# pi_rgb.net
KiCad netlist of a schematic drawn in EAGLE
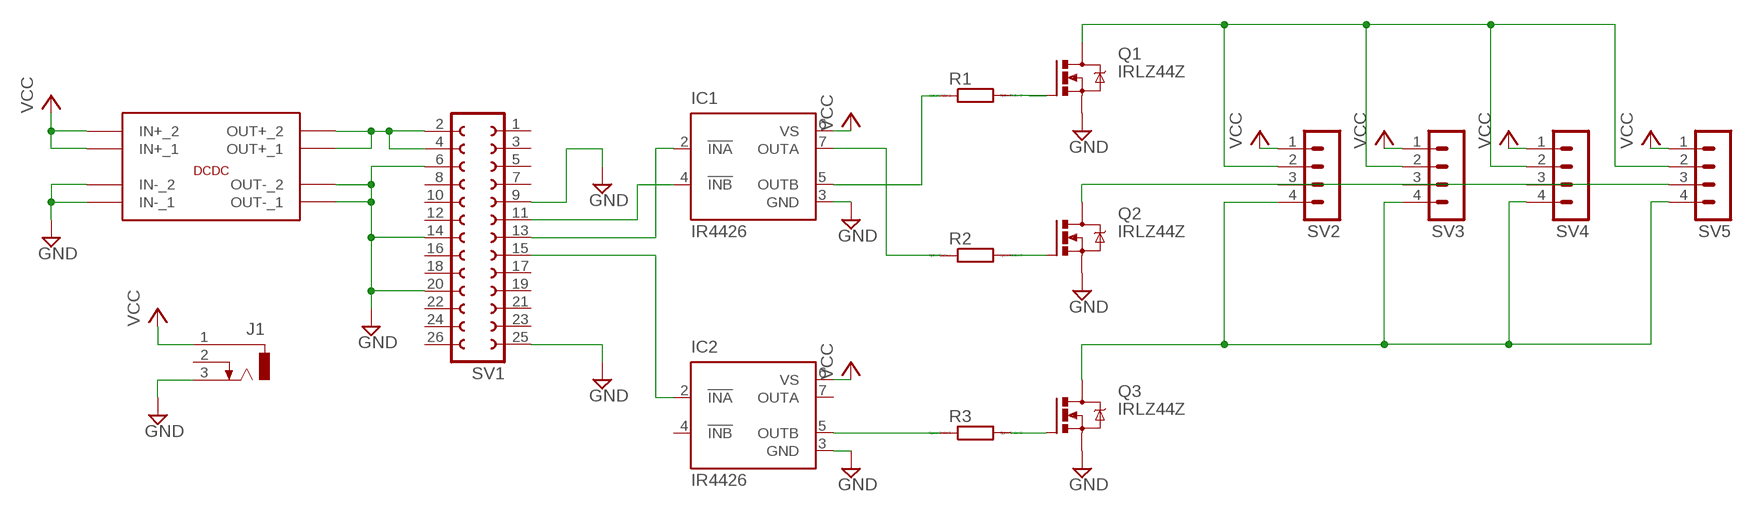
[diagram p0: schematic, sheet 1]

(export (version "E")
  (design (tool "Eeschema 10.0.6"))
  (components
    (comp (ref "5V")
      (value "DCDC")
      (footprint "eagle-import:DCDC")
      (libsource (lib "eagle-import") (part "DCDC"))
    )
    (comp (ref "IC1")
      (value "IR4426")
      (footprint "eagle-import:DIL08")
      (fields (field (name "MF") "INTERNATIONAL RECTIFIER(IR)") (field (name "MPN") "IR4426PBF"))
      (libsource (lib "eagle-import") (part "IR4426"))
    )
    (comp (ref "IC2")
      (value "IR4426")
      (footprint "eagle-import:DIL08")
      (fields (field (name "MF") "INTERNATIONAL RECTIFIER(IR)") (field (name "MPN") "IR4426PBF"))
      (libsource (lib "eagle-import") (part "IR4426"))
    )
    (comp (ref "J1")
      (value "DCJ0303")
      (footprint "eagle-import:DCJ0303")
      (libsource (lib "eagle-import") (part "DCJ0303"))
    )
    (comp (ref "Q1")
      (value "IRLZ44Z")
      (footprint "eagle-import:TO220BV")
      (libsource (lib "eagle-import") (part "IRLZ44Z"))
    )
    (comp (ref "Q2")
      (value "IRLZ44Z")
      (footprint "eagle-import:TO220BV")
      (libsource (lib "eagle-import") (part "IRLZ44Z"))
    )
    (comp (ref "Q3")
      (value "IRLZ44Z")
      (footprint "eagle-import:TO220BV")
      (libsource (lib "eagle-import") (part "IRLZ44Z"))
    )
    (comp (ref "R1")
      (value "R-EU_0204_5")
      (footprint "eagle-import:0204_5")
      (libsource (lib "eagle-import") (part "R-EU_0204_5"))
    )
    (comp (ref "R2")
      (value "R-EU_0204_5")
      (footprint "eagle-import:0204_5")
      (libsource (lib "eagle-import") (part "R-EU_0204_5"))
    )
    (comp (ref "R3")
      (value "R-EU_0204_5")
      (footprint "eagle-import:0204_5")
      (libsource (lib "eagle-import") (part "R-EU_0204_5"))
    )
    (comp (ref "SV1")
      (value "FE13-2")
      (footprint "eagle-import:FE13-2")
      (libsource (lib "eagle-import") (part "FE13-2"))
    )
    (comp (ref "SV2")
      (value "MA04-1")
      (footprint "eagle-import:MA04-1")
      (libsource (lib "eagle-import") (part "MA04-1"))
    )
    (comp (ref "SV3")
      (value "MA04-1")
      (footprint "eagle-import:MA04-1")
      (libsource (lib "eagle-import") (part "MA04-1"))
    )
    (comp (ref "SV4")
      (value "MA04-1")
      (footprint "eagle-import:MA04-1")
      (libsource (lib "eagle-import") (part "MA04-1"))
    )
    (comp (ref "SV5")
      (value "MA04-1")
      (footprint "eagle-import:MA04-1")
      (libsource (lib "eagle-import") (part "MA04-1"))
    )
  )
  (nets
    (net (code "1") (name "GND") (class "Default")
      (node (ref "5V") (pin "IN-_1") (pinfunction "IN-_1_IN-_1") (pintype "bidirectional"))
      (node (ref "5V") (pin "IN-_2") (pinfunction "IN-_2_IN-_2") (pintype "bidirectional"))
      (node (ref "5V") (pin "OUT-_1") (pinfunction "OUT-_1_OUT-_1") (pintype "bidirectional"))
      (node (ref "5V") (pin "OUT-_2") (pinfunction "OUT-_2_OUT-_2") (pintype "bidirectional"))
      (node (ref "IC1") (pin "3") (pinfunction "GND_3") (pintype "power_in"))
      (node (ref "IC2") (pin "3") (pinfunction "GND_3") (pintype "power_in"))
      (node (ref "J1") (pin "3") (pinfunction "3_3") (pintype "passive"))
      (node (ref "Q1") (pin "S") (pinfunction "S_S") (pintype "passive"))
      (node (ref "Q2") (pin "S") (pinfunction "S_S") (pintype "passive"))
      (node (ref "Q3") (pin "S") (pinfunction "S_S") (pintype "passive"))
      (node (ref "SV1") (pin "14") (pinfunction "14_14") (pintype "passive"))
      (node (ref "SV1") (pin "20") (pinfunction "20_20") (pintype "passive"))
      (node (ref "SV1") (pin "25") (pinfunction "25_25") (pintype "passive"))
      (node (ref "SV1") (pin "6") (pinfunction "6_6") (pintype "passive"))
      (node (ref "SV1") (pin "9") (pinfunction "9_9") (pintype "passive"))
    )
    (net (code "2") (name "Net-(5V-OUT+_1)") (class "Default")
      (node (ref "5V") (pin "OUT+2") (pinfunction "OUT+_1_OUT+2") (pintype "bidirectional"))
      (node (ref "5V") (pin "OUT+_1") (pinfunction "OUT+_2_OUT+_1") (pintype "bidirectional"))
      (node (ref "SV1") (pin "2") (pinfunction "2_2") (pintype "passive"))
      (node (ref "SV1") (pin "4") (pinfunction "4_4") (pintype "passive"))
    )
    (net (code "3") (name "Net-(IC1-OUTA)") (class "Default")
      (node (ref "IC1") (pin "7") (pinfunction "OUTA_7") (pintype "output"))
      (node (ref "R2") (pin "1") (pinfunction "1_1") (pintype "passive"))
    )
    (net (code "4") (name "Net-(IC1-OUTB)") (class "Default")
      (node (ref "IC1") (pin "5") (pinfunction "OUTB_5") (pintype "output"))
      (node (ref "R1") (pin "1") (pinfunction "1_1") (pintype "passive"))
    )
    (net (code "5") (name "Net-(IC1-~{INA})") (class "Default")
      (node (ref "IC1") (pin "2") (pinfunction "~{INA}_2") (pintype "input"))
      (node (ref "SV1") (pin "13") (pinfunction "13_13") (pintype "passive"))
    )
    (net (code "6") (name "Net-(IC1-~{INB})") (class "Default")
      (node (ref "IC1") (pin "4") (pinfunction "~{INB}_4") (pintype "input"))
      (node (ref "SV1") (pin "11") (pinfunction "11_11") (pintype "passive"))
    )
    (net (code "7") (name "Net-(IC2-OUTB)") (class "Default")
      (node (ref "IC2") (pin "5") (pinfunction "OUTB_5") (pintype "output"))
      (node (ref "R3") (pin "1") (pinfunction "1_1") (pintype "passive"))
    )
    (net (code "8") (name "Net-(IC2-~{INA})") (class "Default")
      (node (ref "IC2") (pin "2") (pinfunction "~{INA}_2") (pintype "input"))
      (node (ref "SV1") (pin "15") (pinfunction "15_15") (pintype "passive"))
    )
    (net (code "9") (name "Net-(Q1-PadD)") (class "Default")
      (node (ref "Q1") (pin "D") (pinfunction "D_D") (pintype "passive"))
      (node (ref "SV2") (pin "2") (pinfunction "2_2") (pintype "passive"))
      (node (ref "SV3") (pin "2") (pinfunction "2_2") (pintype "passive"))
      (node (ref "SV4") (pin "2") (pinfunction "2_2") (pintype "passive"))
      (node (ref "SV5") (pin "2") (pinfunction "2_2") (pintype "passive"))
    )
    (net (code "10") (name "Net-(Q1-PadG)") (class "Default")
      (node (ref "Q1") (pin "G") (pinfunction "G_G") (pintype "passive"))
      (node (ref "R1") (pin "2") (pinfunction "2_2") (pintype "passive"))
    )
    (net (code "11") (name "Net-(Q2-PadD)") (class "Default")
      (node (ref "Q2") (pin "D") (pinfunction "D_D") (pintype "passive"))
      (node (ref "SV2") (pin "3") (pinfunction "3_3") (pintype "passive"))
      (node (ref "SV3") (pin "3") (pinfunction "3_3") (pintype "passive"))
      (node (ref "SV4") (pin "3") (pinfunction "3_3") (pintype "passive"))
      (node (ref "SV5") (pin "3") (pinfunction "3_3") (pintype "passive"))
    )
    (net (code "12") (name "Net-(Q2-PadG)") (class "Default")
      (node (ref "Q2") (pin "G") (pinfunction "G_G") (pintype "passive"))
      (node (ref "R2") (pin "2") (pinfunction "2_2") (pintype "passive"))
    )
    (net (code "13") (name "Net-(Q3-PadD)") (class "Default")
      (node (ref "Q3") (pin "D") (pinfunction "D_D") (pintype "passive"))
      (node (ref "SV2") (pin "4") (pinfunction "4_4") (pintype "passive"))
      (node (ref "SV3") (pin "4") (pinfunction "4_4") (pintype "passive"))
      (node (ref "SV4") (pin "4") (pinfunction "4_4") (pintype "passive"))
      (node (ref "SV5") (pin "4") (pinfunction "4_4") (pintype "passive"))
    )
    (net (code "14") (name "Net-(Q3-PadG)") (class "Default")
      (node (ref "Q3") (pin "G") (pinfunction "G_G") (pintype "passive"))
      (node (ref "R3") (pin "2") (pinfunction "2_2") (pintype "passive"))
    )
    (net (code "15") (name "VCC") (class "Default")
      (node (ref "5V") (pin "IN+_1") (pinfunction "IN+_1_IN+_1") (pintype "bidirectional"))
      (node (ref "5V") (pin "IN+_2") (pinfunction "IN+_2_IN+_2") (pintype "bidirectional"))
      (node (ref "IC1") (pin "6") (pinfunction "VS_6") (pintype "power_in"))
      (node (ref "IC2") (pin "6") (pinfunction "VS_6") (pintype "power_in"))
      (node (ref "J1") (pin "1") (pinfunction "1_1") (pintype "passive"))
      (node (ref "SV2") (pin "1") (pinfunction "1_1") (pintype "passive"))
      (node (ref "SV3") (pin "1") (pinfunction "1_1") (pintype "passive"))
      (node (ref "SV4") (pin "1") (pinfunction "1_1") (pintype "passive"))
      (node (ref "SV5") (pin "1") (pinfunction "1_1") (pintype "passive"))
    )
    (net (code "16") (name "unconnected-(IC2-OUTA-Pad7)") (class "Default")
      (node (ref "IC2") (pin "7") (pinfunction "OUTA_7") (pintype "output"))
    )
    (net (code "17") (name "unconnected-(IC2-~{INB}-Pad4)") (class "Default")
      (node (ref "IC2") (pin "4") (pinfunction "~{INB}_4") (pintype "input"))
    )
    (net (code "18") (name "unconnected-(J1-Pad2)") (class "Default")
      (node (ref "J1") (pin "2") (pinfunction "2_2") (pintype "passive"))
    )
    (net (code "19") (name "unconnected-(SV1-Pad1)") (class "Default")
      (node (ref "SV1") (pin "1") (pinfunction "1_1") (pintype "passive"))
    )
    (net (code "20") (name "unconnected-(SV1-Pad3)") (class "Default")
      (node (ref "SV1") (pin "3") (pinfunction "3_3") (pintype "passive"))
    )
    (net (code "21") (name "unconnected-(SV1-Pad5)") (class "Default")
      (node (ref "SV1") (pin "5") (pinfunction "5_5") (pintype "passive"))
    )
    (net (code "22") (name "unconnected-(SV1-Pad7)") (class "Default")
      (node (ref "SV1") (pin "7") (pinfunction "7_7") (pintype "passive"))
    )
    (net (code "23") (name "unconnected-(SV1-Pad8)") (class "Default")
      (node (ref "SV1") (pin "8") (pinfunction "8_8") (pintype "passive"))
    )
    (net (code "24") (name "unconnected-(SV1-Pad10)") (class "Default")
      (node (ref "SV1") (pin "10") (pinfunction "10_10") (pintype "passive"))
    )
    (net (code "25") (name "unconnected-(SV1-Pad12)") (class "Default")
      (node (ref "SV1") (pin "12") (pinfunction "12_12") (pintype "passive"))
    )
    (net (code "26") (name "unconnected-(SV1-Pad16)") (class "Default")
      (node (ref "SV1") (pin "16") (pinfunction "16_16") (pintype "passive"))
    )
    (net (code "27") (name "unconnected-(SV1-Pad17)") (class "Default")
      (node (ref "SV1") (pin "17") (pinfunction "17_17") (pintype "passive"))
    )
    (net (code "28") (name "unconnected-(SV1-Pad18)") (class "Default")
      (node (ref "SV1") (pin "18") (pinfunction "18_18") (pintype "passive"))
    )
    (net (code "29") (name "unconnected-(SV1-Pad19)") (class "Default")
      (node (ref "SV1") (pin "19") (pinfunction "19_19") (pintype "passive"))
    )
    (net (code "30") (name "unconnected-(SV1-Pad21)") (class "Default")
      (node (ref "SV1") (pin "21") (pinfunction "21_21") (pintype "passive"))
    )
    (net (code "31") (name "unconnected-(SV1-Pad22)") (class "Default")
      (node (ref "SV1") (pin "22") (pinfunction "22_22") (pintype "passive"))
    )
    (net (code "32") (name "unconnected-(SV1-Pad23)") (class "Default")
      (node (ref "SV1") (pin "23") (pinfunction "23_23") (pintype "passive"))
    )
    (net (code "33") (name "unconnected-(SV1-Pad24)") (class "Default")
      (node (ref "SV1") (pin "24") (pinfunction "24_24") (pintype "passive"))
    )
    (net (code "34") (name "unconnected-(SV1-Pad26)") (class "Default")
      (node (ref "SV1") (pin "26") (pinfunction "26_26") (pintype "passive"))
    )
  )
)
